# MCU.net
KiCad netlist of a schematic drawn in Altium Designer
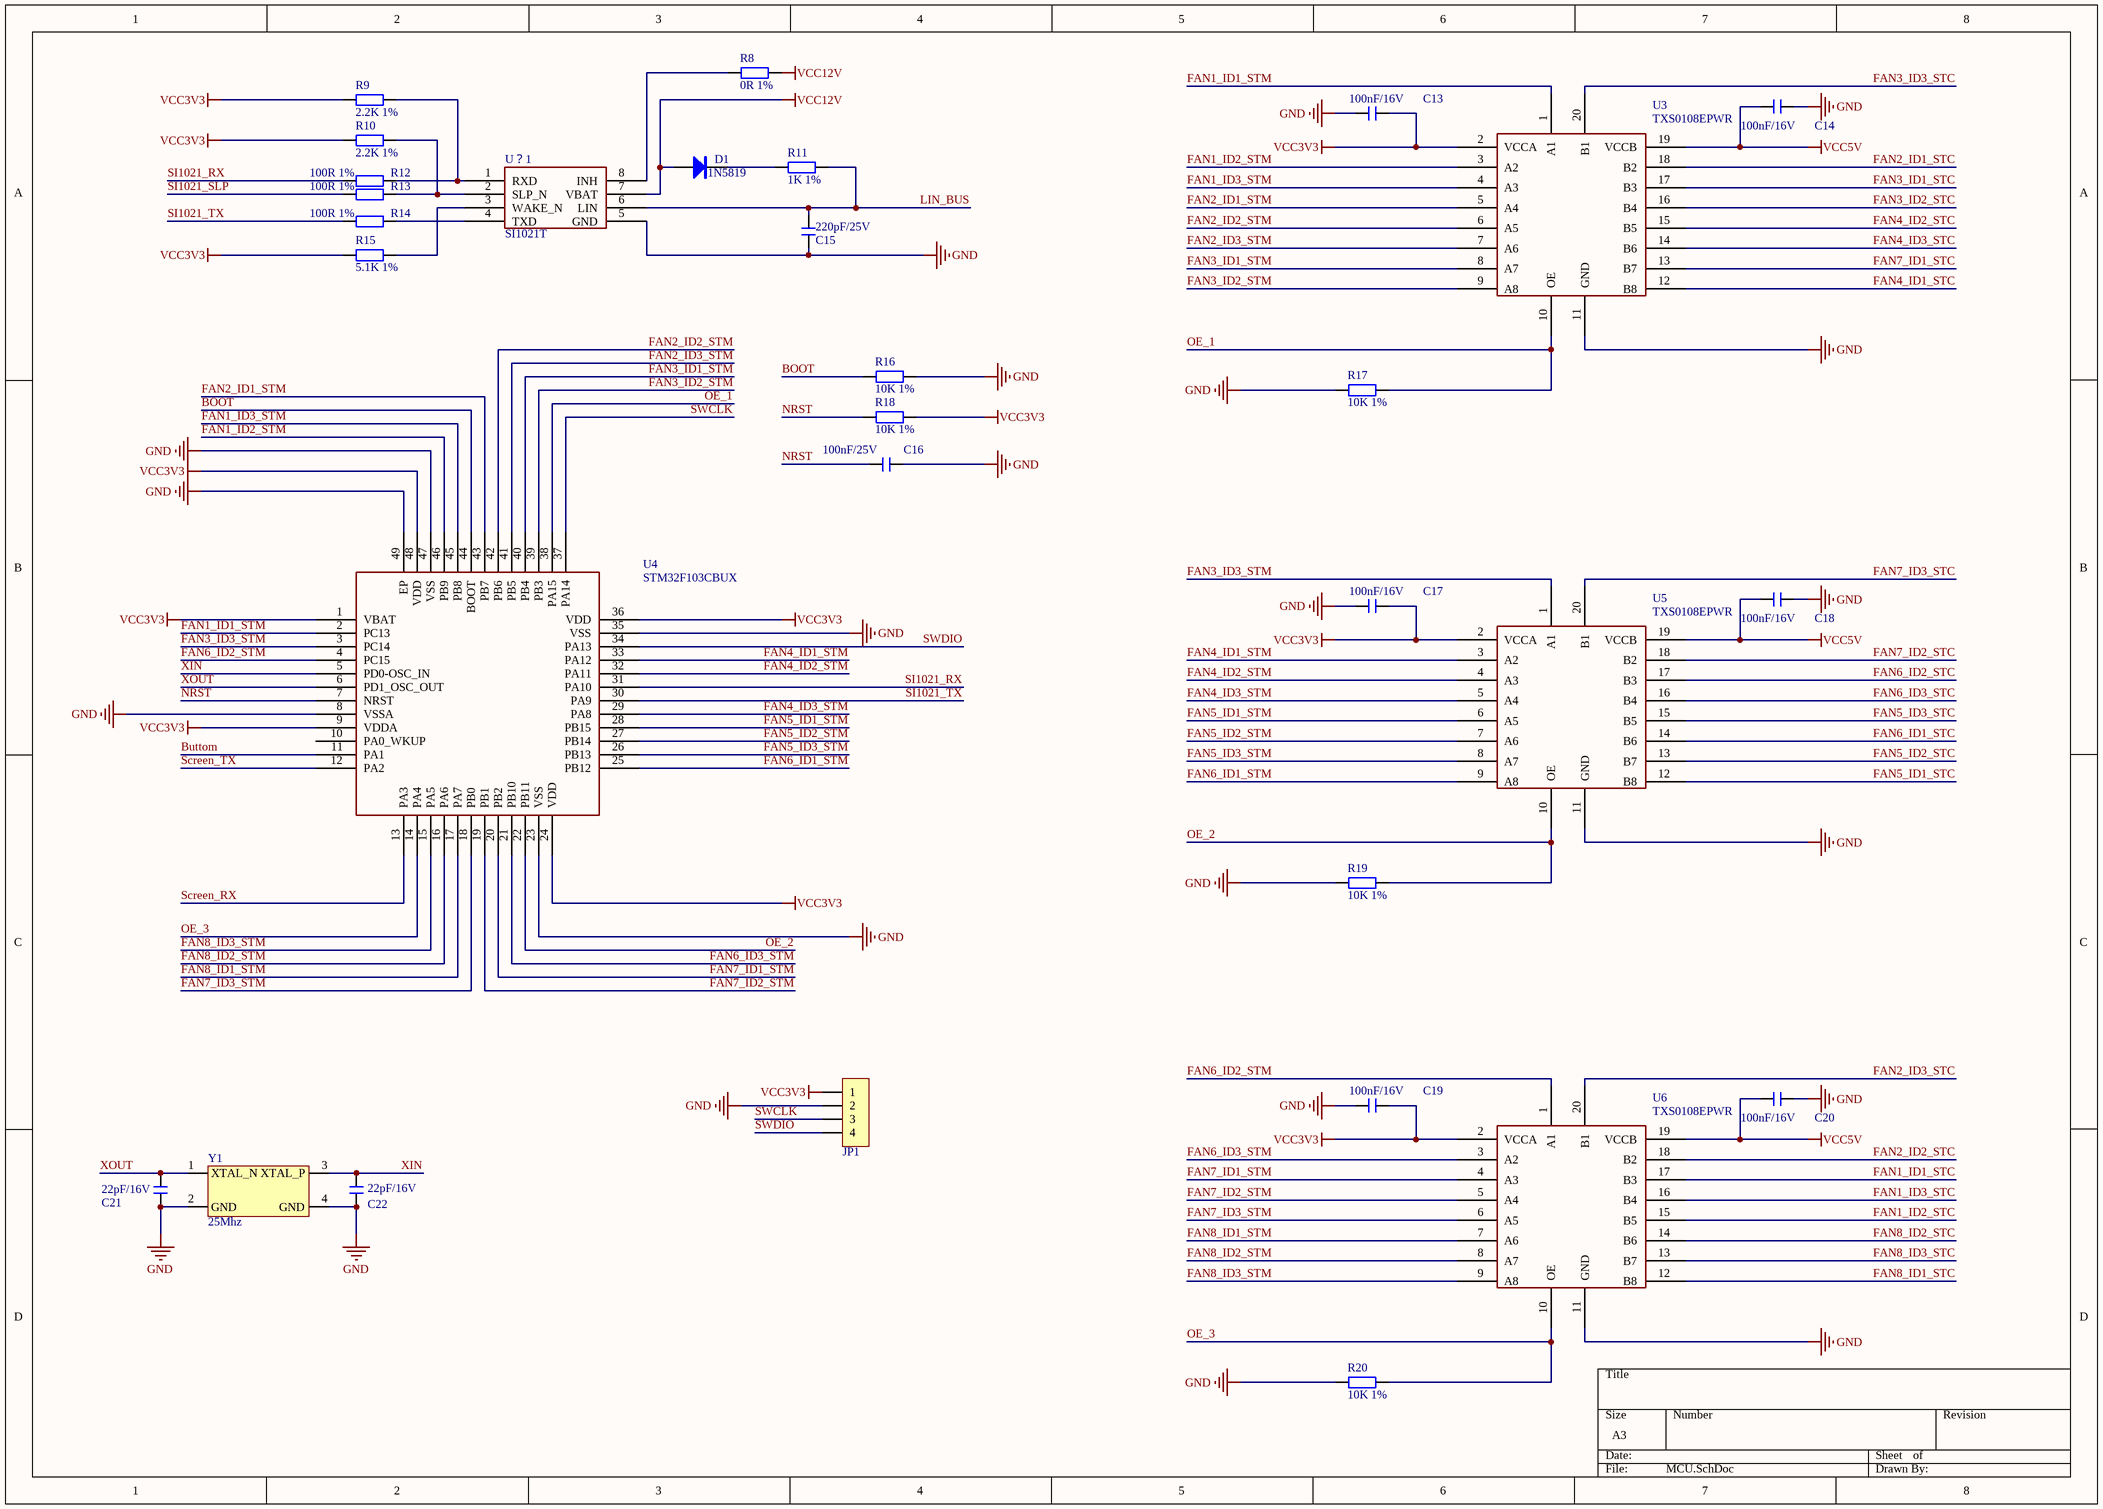
[diagram p0: MCU.SchDoc]

(export (version "E")
  (design (tool "Eeschema 10.0.6"))
  (components
    (comp (ref "C13")
      (value "100nF/16V")
      (footprint "c0603_l")
      (description "无极性贴片电容")
      (fields (field (name "版权归属") "源创客"))
      (libsource (lib "Capacitor") (part "C"))
    )
    (comp (ref "C14")
      (value "100nF/16V")
      (footprint "c0603_l")
      (description "无极性贴片电容")
      (fields (field (name "版权归属") "源创客"))
      (libsource (lib "Capacitor") (part "C"))
    )
    (comp (ref "C15")
      (value "220pF/25V")
      (footprint "c0603_l")
      (description "无极性贴片电容")
      (fields (field (name "版权归属") "源创客"))
      (libsource (lib "Capacitor") (part "C"))
    )
    (comp (ref "C16")
      (value "100nF/25V")
      (footprint "c0603_l")
      (description "无极性贴片电容")
      (fields (field (name "版权归属") "源创客"))
      (libsource (lib "Capacitor") (part "C"))
    )
    (comp (ref "C17")
      (value "100nF/16V")
      (footprint "c0603_l")
      (description "无极性贴片电容")
      (fields (field (name "版权归属") "源创客"))
      (libsource (lib "Capacitor") (part "C"))
    )
    (comp (ref "C18")
      (value "100nF/16V")
      (footprint "c0603_l")
      (description "无极性贴片电容")
      (fields (field (name "版权归属") "源创客"))
      (libsource (lib "Capacitor") (part "C"))
    )
    (comp (ref "C19")
      (value "100nF/16V")
      (footprint "c0603_l")
      (description "无极性贴片电容")
      (fields (field (name "版权归属") "源创客"))
      (libsource (lib "Capacitor") (part "C"))
    )
    (comp (ref "C20")
      (value "100nF/16V")
      (footprint "c0603_l")
      (description "无极性贴片电容")
      (fields (field (name "版权归属") "源创客"))
      (libsource (lib "Capacitor") (part "C"))
    )
    (comp (ref "C21")
      (value "22pF/16V")
      (footprint "c0603_l")
      (description "无极性贴片电容")
      (fields (field (name "版权归属") "源创客"))
      (libsource (lib "Capacitor") (part "C"))
    )
    (comp (ref "C22")
      (value "22pF/16V")
      (footprint "c0603_l")
      (description "无极性贴片电容")
      (fields (field (name "版权归属") "源创客"))
      (libsource (lib "Capacitor") (part "C"))
    )
    (comp (ref "D1")
      (value "1N5819")
      (footprint "SOD-323")
      (description "肖特基二极管")
      (fields (field (name "版权归属") "源创客"))
      (libsource (lib "Diode") (part "1N5819"))
    )
    (comp (ref "JP1")
      (value "HDR-1X4")
      (footprint "HDR2.54-WI-4P")
      (description "4P接插件")
      (fields (field (name "版权归属") "源创客"))
      (libsource (lib "Connector-PinHeader") (part "Header 4"))
    )
    (comp (ref "R8")
      (value "0R 1%")
      (footprint "r0603_l")
      (description "贴片电阻")
      (fields (field (name "版权归属") "源创客"))
      (libsource (lib "Resistor") (part "R"))
    )
    (comp (ref "R9")
      (value "2.2K 1%")
      (footprint "r0603_l")
      (description "贴片电阻")
      (fields (field (name "版权归属") "源创客"))
      (libsource (lib "Resistor") (part "R"))
    )
    (comp (ref "R10")
      (value "2.2K 1%")
      (footprint "r0603_l")
      (description "贴片电阻")
      (fields (field (name "版权归属") "源创客"))
      (libsource (lib "Resistor") (part "R"))
    )
    (comp (ref "R11")
      (value "1K 1%")
      (footprint "r0603_l")
      (description "贴片电阻")
      (fields (field (name "版权归属") "源创客"))
      (libsource (lib "Resistor") (part "R"))
    )
    (comp (ref "R12")
      (value "100R 1%")
      (footprint "r0603_l")
      (description "贴片电阻")
      (fields (field (name "版权归属") "源创客"))
      (libsource (lib "Resistor") (part "R"))
    )
    (comp (ref "R13")
      (value "100R 1%")
      (footprint "r0603_l")
      (description "贴片电阻")
      (fields (field (name "版权归属") "源创客"))
      (libsource (lib "Resistor") (part "R"))
    )
    (comp (ref "R14")
      (value "100R 1%")
      (footprint "r0603_l")
      (description "贴片电阻")
      (fields (field (name "版权归属") "源创客"))
      (libsource (lib "Resistor") (part "R"))
    )
    (comp (ref "R15")
      (value "5.1K 1%")
      (footprint "r0603_l")
      (description "贴片电阻")
      (fields (field (name "版权归属") "源创客"))
      (libsource (lib "Resistor") (part "R"))
    )
    (comp (ref "R16")
      (value "10K 1%")
      (footprint "r0603_l")
      (description "贴片电阻")
      (fields (field (name "版权归属") "源创客"))
      (libsource (lib "Resistor") (part "R"))
    )
    (comp (ref "R17")
      (value "10K 1%")
      (footprint "r0603_l")
      (description "贴片电阻")
      (fields (field (name "版权归属") "源创客"))
      (libsource (lib "Resistor") (part "R"))
    )
    (comp (ref "R18")
      (value "10K 1%")
      (footprint "r0603_l")
      (description "贴片电阻")
      (fields (field (name "版权归属") "源创客"))
      (libsource (lib "Resistor") (part "R"))
    )
    (comp (ref "R19")
      (value "10K 1%")
      (footprint "r0603_l")
      (description "贴片电阻")
      (fields (field (name "版权归属") "源创客"))
      (libsource (lib "Resistor") (part "R"))
    )
    (comp (ref "R20")
      (value "10K 1%")
      (footprint "r0603_l")
      (description "贴片电阻")
      (fields (field (name "版权归属") "源创客"))
      (libsource (lib "Resistor") (part "R"))
    )
    (comp (ref "U3")
      (value "TXS0108EPWR")
      (footprint "TXS0108ERGYR")
      (description "适用于开漏和推挽应用的八位双向电压电平转换器")
      (libsource (lib "移位寄存器") (part "TXS0108EPWR"))
    )
    (comp (ref "U4")
      (value "STM32F103CBUX")
      (footprint "QFN48 7X7_M")
      (libsource (lib "MCU") (part "STM32F103CBUX"))
    )
    (comp (ref "U5")
      (value "TXS0108EPWR")
      (footprint "TXS0108ERGYR")
      (description "适用于开漏和推挽应用的八位双向电压电平转换器")
      (libsource (lib "移位寄存器") (part "TXS0108EPWR"))
    )
    (comp (ref "U6")
      (value "TXS0108EPWR")
      (footprint "TXS0108ERGYR")
      (description "适用于开漏和推挽应用的八位双向电压电平转换器")
      (libsource (lib "移位寄存器") (part "TXS0108EPWR"))
    )
    (comp (ref "U？1")
      (value "SI1021T")
      (footprint "SOP8")
      (description "SI1021T LIN收发器")
      (libsource (lib "transceiver") (part "SI1021T"))
    )
    (comp (ref "Y1") (value "25Mhz") (footprint "OSC 3225-4P") (libsource (lib "Crystal") (part "Crystal")))
  )
  (nets
    (net (code "1") (name "/BOOT") (class "Default")
      (node (ref "R16") (pin "1") (pinfunction "1_1") (pintype "passive"))
      (node (ref "U4") (pin "44") (pinfunction "BOOT_44") (pintype "passive"))
    )
    (net (code "2") (name "/Buttom") (class "Default")
      (node (ref "U4") (pin "11") (pinfunction "PA1_11") (pintype "passive"))
    )
    (net (code "3") (name "/FAN1_ID1_STC") (class "Default")
      (node (ref "U6") (pin "17") (pinfunction "B3_17") (pintype "passive"))
    )
    (net (code "4") (name "/FAN1_ID1_STM") (class "Default")
      (node (ref "U3") (pin "1") (pinfunction "A1_1") (pintype "passive"))
      (node (ref "U4") (pin "2") (pinfunction "PC13_2") (pintype "passive"))
    )
    (net (code "5") (name "/FAN1_ID2_STC") (class "Default")
      (node (ref "U6") (pin "15") (pinfunction "B5_15") (pintype "passive"))
    )
    (net (code "6") (name "/FAN1_ID2_STM") (class "Default")
      (node (ref "U3") (pin "3") (pinfunction "A2_3") (pintype "passive"))
      (node (ref "U4") (pin "46") (pinfunction "PB9_46") (pintype "passive"))
    )
    (net (code "7") (name "/FAN1_ID3_STC") (class "Default")
      (node (ref "U6") (pin "16") (pinfunction "B4_16") (pintype "passive"))
    )
    (net (code "8") (name "/FAN1_ID3_STM") (class "Default")
      (node (ref "U3") (pin "4") (pinfunction "A3_4") (pintype "passive"))
      (node (ref "U4") (pin "45") (pinfunction "PB8_45") (pintype "passive"))
    )
    (net (code "9") (name "/FAN2_ID1_STC") (class "Default")
      (node (ref "U3") (pin "18") (pinfunction "B2_18") (pintype "passive"))
    )
    (net (code "10") (name "/FAN2_ID1_STM") (class "Default")
      (node (ref "U3") (pin "5") (pinfunction "A4_5") (pintype "passive"))
      (node (ref "U4") (pin "43") (pinfunction "PB7_43") (pintype "passive"))
    )
    (net (code "11") (name "/FAN2_ID2_STC") (class "Default")
      (node (ref "U6") (pin "18") (pinfunction "B2_18") (pintype "passive"))
    )
    (net (code "12") (name "/FAN2_ID2_STM") (class "Default")
      (node (ref "U3") (pin "6") (pinfunction "A5_6") (pintype "passive"))
      (node (ref "U4") (pin "42") (pinfunction "PB6_42") (pintype "passive"))
    )
    (net (code "13") (name "/FAN2_ID3_STC") (class "Default")
      (node (ref "U6") (pin "20") (pinfunction "B1_20") (pintype "passive"))
    )
    (net (code "14") (name "/FAN2_ID3_STM") (class "Default")
      (node (ref "U3") (pin "7") (pinfunction "A6_7") (pintype "passive"))
      (node (ref "U4") (pin "41") (pinfunction "PB5_41") (pintype "passive"))
    )
    (net (code "15") (name "/FAN3_ID1_STC") (class "Default")
      (node (ref "U3") (pin "17") (pinfunction "B3_17") (pintype "passive"))
    )
    (net (code "16") (name "/FAN3_ID1_STM") (class "Default")
      (node (ref "U3") (pin "8") (pinfunction "A7_8") (pintype "passive"))
      (node (ref "U4") (pin "40") (pinfunction "PB4_40") (pintype "passive"))
    )
    (net (code "17") (name "/FAN3_ID2_STC") (class "Default")
      (node (ref "U3") (pin "16") (pinfunction "B4_16") (pintype "passive"))
    )
    (net (code "18") (name "/FAN3_ID2_STM") (class "Default")
      (node (ref "U3") (pin "9") (pinfunction "A8_9") (pintype "passive"))
      (node (ref "U4") (pin "39") (pinfunction "PB3_39") (pintype "passive"))
    )
    (net (code "19") (name "/FAN3_ID3_STC") (class "Default")
      (node (ref "U3") (pin "20") (pinfunction "B1_20") (pintype "passive"))
    )
    (net (code "20") (name "/FAN3_ID3_STM") (class "Default")
      (node (ref "U4") (pin "3") (pinfunction "PC14_3") (pintype "passive"))
      (node (ref "U5") (pin "1") (pinfunction "A1_1") (pintype "passive"))
    )
    (net (code "21") (name "/FAN4_ID1_STC") (class "Default")
      (node (ref "U3") (pin "12") (pinfunction "B8_12") (pintype "passive"))
    )
    (net (code "22") (name "/FAN4_ID1_STM") (class "Default")
      (node (ref "U4") (pin "33") (pinfunction "PA12_33") (pintype "passive"))
      (node (ref "U5") (pin "3") (pinfunction "A2_3") (pintype "passive"))
    )
    (net (code "23") (name "/FAN4_ID2_STC") (class "Default")
      (node (ref "U3") (pin "15") (pinfunction "B5_15") (pintype "passive"))
    )
    (net (code "24") (name "/FAN4_ID2_STM") (class "Default")
      (node (ref "U4") (pin "32") (pinfunction "PA11_32") (pintype "passive"))
      (node (ref "U5") (pin "4") (pinfunction "A3_4") (pintype "passive"))
    )
    (net (code "25") (name "/FAN4_ID3_STC") (class "Default")
      (node (ref "U3") (pin "14") (pinfunction "B6_14") (pintype "passive"))
    )
    (net (code "26") (name "/FAN4_ID3_STM") (class "Default")
      (node (ref "U4") (pin "29") (pinfunction "PA8_29") (pintype "passive"))
      (node (ref "U5") (pin "5") (pinfunction "A4_5") (pintype "passive"))
    )
    (net (code "27") (name "/FAN5_ID1_STC") (class "Default")
      (node (ref "U5") (pin "12") (pinfunction "B8_12") (pintype "passive"))
    )
    (net (code "28") (name "/FAN5_ID1_STM") (class "Default")
      (node (ref "U4") (pin "28") (pinfunction "PB15_28") (pintype "passive"))
      (node (ref "U5") (pin "6") (pinfunction "A5_6") (pintype "passive"))
    )
    (net (code "29") (name "/FAN5_ID2_STC") (class "Default")
      (node (ref "U5") (pin "13") (pinfunction "B7_13") (pintype "passive"))
    )
    (net (code "30") (name "/FAN5_ID2_STM") (class "Default")
      (node (ref "U4") (pin "27") (pinfunction "PB14_27") (pintype "passive"))
      (node (ref "U5") (pin "7") (pinfunction "A6_7") (pintype "passive"))
    )
    (net (code "31") (name "/FAN5_ID3_STC") (class "Default")
      (node (ref "U5") (pin "15") (pinfunction "B5_15") (pintype "passive"))
    )
    (net (code "32") (name "/FAN5_ID3_STM") (class "Default")
      (node (ref "U4") (pin "26") (pinfunction "PB13_26") (pintype "passive"))
      (node (ref "U5") (pin "8") (pinfunction "A7_8") (pintype "passive"))
    )
    (net (code "33") (name "/FAN6_ID1_STC") (class "Default")
      (node (ref "U5") (pin "14") (pinfunction "B6_14") (pintype "passive"))
    )
    (net (code "34") (name "/FAN6_ID1_STM") (class "Default")
      (node (ref "U4") (pin "25") (pinfunction "PB12_25") (pintype "passive"))
      (node (ref "U5") (pin "9") (pinfunction "A8_9") (pintype "passive"))
    )
    (net (code "35") (name "/FAN6_ID2_STC") (class "Default")
      (node (ref "U5") (pin "17") (pinfunction "B3_17") (pintype "passive"))
    )
    (net (code "36") (name "/FAN6_ID2_STM") (class "Default")
      (node (ref "U4") (pin "4") (pinfunction "PC15_4") (pintype "passive"))
      (node (ref "U6") (pin "1") (pinfunction "A1_1") (pintype "passive"))
    )
    (net (code "37") (name "/FAN6_ID3_STC") (class "Default")
      (node (ref "U5") (pin "16") (pinfunction "B4_16") (pintype "passive"))
    )
    (net (code "38") (name "/FAN6_ID3_STM") (class "Default")
      (node (ref "U4") (pin "21") (pinfunction "PB10_21") (pintype "passive"))
      (node (ref "U6") (pin "3") (pinfunction "A2_3") (pintype "passive"))
    )
    (net (code "39") (name "/FAN7_ID1_STC") (class "Default")
      (node (ref "U3") (pin "13") (pinfunction "B7_13") (pintype "passive"))
    )
    (net (code "40") (name "/FAN7_ID1_STM") (class "Default")
      (node (ref "U4") (pin "20") (pinfunction "PB2_20") (pintype "passive"))
      (node (ref "U6") (pin "4") (pinfunction "A3_4") (pintype "passive"))
    )
    (net (code "41") (name "/FAN7_ID2_STC") (class "Default")
      (node (ref "U5") (pin "18") (pinfunction "B2_18") (pintype "passive"))
    )
    (net (code "42") (name "/FAN7_ID2_STM") (class "Default")
      (node (ref "U4") (pin "19") (pinfunction "PB1_19") (pintype "passive"))
      (node (ref "U6") (pin "5") (pinfunction "A4_5") (pintype "passive"))
    )
    (net (code "43") (name "/FAN7_ID3_STC") (class "Default")
      (node (ref "U5") (pin "20") (pinfunction "B1_20") (pintype "passive"))
    )
    (net (code "44") (name "/FAN7_ID3_STM") (class "Default")
      (node (ref "U4") (pin "18") (pinfunction "PB0_18") (pintype "passive"))
      (node (ref "U6") (pin "6") (pinfunction "A5_6") (pintype "passive"))
    )
    (net (code "45") (name "/FAN8_ID1_STC") (class "Default")
      (node (ref "U6") (pin "12") (pinfunction "B8_12") (pintype "passive"))
    )
    (net (code "46") (name "/FAN8_ID1_STM") (class "Default")
      (node (ref "U4") (pin "17") (pinfunction "PA7_17") (pintype "passive"))
      (node (ref "U6") (pin "7") (pinfunction "A6_7") (pintype "passive"))
    )
    (net (code "47") (name "/FAN8_ID2_STC") (class "Default")
      (node (ref "U6") (pin "14") (pinfunction "B6_14") (pintype "passive"))
    )
    (net (code "48") (name "/FAN8_ID2_STM") (class "Default")
      (node (ref "U4") (pin "16") (pinfunction "PA6_16") (pintype "passive"))
      (node (ref "U6") (pin "8") (pinfunction "A7_8") (pintype "passive"))
    )
    (net (code "49") (name "/FAN8_ID3_STC") (class "Default")
      (node (ref "U6") (pin "13") (pinfunction "B7_13") (pintype "passive"))
    )
    (net (code "50") (name "/FAN8_ID3_STM") (class "Default")
      (node (ref "U4") (pin "15") (pinfunction "PA5_15") (pintype "passive"))
      (node (ref "U6") (pin "9") (pinfunction "A8_9") (pintype "passive"))
    )
    (net (code "51") (name "/LIN_BUS") (class "Default")
      (node (ref "C15") (pin "2") (pinfunction "2_2") (pintype "passive"))
      (node (ref "R11") (pin "1") (pinfunction "1_1") (pintype "passive"))
      (node (ref "U？1") (pin "6") (pinfunction "LIN_6") (pintype "passive"))
    )
    (net (code "52") (name "/NRST") (class "Default")
      (node (ref "C16") (pin "2") (pinfunction "2_2") (pintype "passive"))
      (node (ref "R18") (pin "1") (pinfunction "1_1") (pintype "passive"))
      (node (ref "U4") (pin "7") (pinfunction "NRST_7") (pintype "passive"))
    )
    (net (code "53") (name "/OE_1") (class "Default")
      (node (ref "R17") (pin "2") (pinfunction "2_2") (pintype "passive"))
      (node (ref "U3") (pin "10") (pinfunction "OE_10") (pintype "passive"))
      (node (ref "U4") (pin "38") (pinfunction "PA15_38") (pintype "passive"))
    )
    (net (code "54") (name "/OE_2") (class "Default")
      (node (ref "R19") (pin "2") (pinfunction "2_2") (pintype "passive"))
      (node (ref "U4") (pin "22") (pinfunction "PB11_22") (pintype "passive"))
      (node (ref "U5") (pin "10") (pinfunction "OE_10") (pintype "passive"))
    )
    (net (code "55") (name "/OE_3") (class "Default")
      (node (ref "R20") (pin "2") (pinfunction "2_2") (pintype "passive"))
      (node (ref "U4") (pin "14") (pinfunction "PA4_14") (pintype "passive"))
      (node (ref "U6") (pin "10") (pinfunction "OE_10") (pintype "passive"))
    )
    (net (code "56") (name "/SI1021_RX") (class "Default")
      (node (ref "R12") (pin "1") (pinfunction "1_1") (pintype "passive"))
      (node (ref "U4") (pin "31") (pinfunction "PA10_31") (pintype "passive"))
    )
    (net (code "57") (name "/SI1021_SLP") (class "Default")
      (node (ref "R13") (pin "1") (pinfunction "1_1") (pintype "passive"))
    )
    (net (code "58") (name "/SI1021_TX") (class "Default")
      (node (ref "R14") (pin "1") (pinfunction "1_1") (pintype "passive"))
      (node (ref "U4") (pin "30") (pinfunction "PA9_30") (pintype "passive"))
    )
    (net (code "59") (name "/SWCLK") (class "Default")
      (node (ref "JP1") (pin "3") (pinfunction "3_3") (pintype "passive"))
      (node (ref "U4") (pin "37") (pinfunction "PA14_37") (pintype "passive"))
    )
    (net (code "60") (name "/SWDIO") (class "Default")
      (node (ref "JP1") (pin "4") (pinfunction "4_4") (pintype "passive"))
      (node (ref "U4") (pin "34") (pinfunction "PA13_34") (pintype "passive"))
    )
    (net (code "61") (name "/Screen_RX") (class "Default")
      (node (ref "U4") (pin "13") (pinfunction "PA3_13") (pintype "passive"))
    )
    (net (code "62") (name "/Screen_TX") (class "Default")
      (node (ref "U4") (pin "12") (pinfunction "PA2_12") (pintype "passive"))
    )
    (net (code "63") (name "/XIN") (class "Default")
      (node (ref "C22") (pin "1") (pinfunction "1_1") (pintype "passive"))
      (node (ref "U4") (pin "5") (pinfunction "PD0-OSC_IN_5") (pintype "passive"))
      (node (ref "Y1") (pin "3") (pinfunction "XTAL_P_3") (pintype "passive"))
    )
    (net (code "64") (name "/XOUT") (class "Default")
      (node (ref "C21") (pin "1") (pinfunction "1_1") (pintype "passive"))
      (node (ref "U4") (pin "6") (pinfunction "PD1_OSC_OUT_6") (pintype "passive"))
      (node (ref "Y1") (pin "1") (pinfunction "XTAL_N_1") (pintype "passive"))
    )
    (net (code "65") (name "GND") (class "Default")
      (node (ref "C13") (pin "2") (pinfunction "2_2") (pintype "passive"))
      (node (ref "C14") (pin "1") (pinfunction "1_1") (pintype "passive"))
      (node (ref "C15") (pin "1") (pinfunction "1_1") (pintype "passive"))
      (node (ref "C16") (pin "1") (pinfunction "1_1") (pintype "passive"))
      (node (ref "C17") (pin "2") (pinfunction "2_2") (pintype "passive"))
      (node (ref "C18") (pin "1") (pinfunction "1_1") (pintype "passive"))
      (node (ref "C19") (pin "2") (pinfunction "2_2") (pintype "passive"))
      (node (ref "C20") (pin "1") (pinfunction "1_1") (pintype "passive"))
      (node (ref "C21") (pin "2") (pinfunction "2_2") (pintype "passive"))
      (node (ref "C22") (pin "2") (pinfunction "2_2") (pintype "passive"))
      (node (ref "JP1") (pin "2") (pinfunction "2_2") (pintype "passive"))
      (node (ref "R16") (pin "2") (pinfunction "2_2") (pintype "passive"))
      (node (ref "R17") (pin "1") (pinfunction "1_1") (pintype "passive"))
      (node (ref "R19") (pin "1") (pinfunction "1_1") (pintype "passive"))
      (node (ref "R20") (pin "1") (pinfunction "1_1") (pintype "passive"))
      (node (ref "U3") (pin "11") (pinfunction "GND_11") (pintype "passive"))
      (node (ref "U4") (pin "23") (pinfunction "VSS_23") (pintype "passive"))
      (node (ref "U4") (pin "35") (pinfunction "VSS_35") (pintype "passive"))
      (node (ref "U4") (pin "47") (pinfunction "VSS_47") (pintype "passive"))
      (node (ref "U4") (pin "49") (pinfunction "EP_49") (pintype "passive"))
      (node (ref "U4") (pin "8") (pinfunction "VSSA_8") (pintype "passive"))
      (node (ref "U5") (pin "11") (pinfunction "GND_11") (pintype "passive"))
      (node (ref "U6") (pin "11") (pinfunction "GND_11") (pintype "passive"))
      (node (ref "U？1") (pin "5") (pinfunction "GND_5") (pintype "passive"))
      (node (ref "Y1") (pin "2") (pinfunction "GND_2") (pintype "passive"))
      (node (ref "Y1") (pin "4") (pinfunction "GND_4") (pintype "passive"))
    )
    (net (code "66") (name "Net-(D1-K)") (class "Default")
      (node (ref "D1") (pin "2") (pinfunction "K_2") (pintype "passive"))
      (node (ref "R11") (pin "2") (pinfunction "2_2") (pintype "passive"))
    )
    (net (code "67") (name "Net-(U？1-INH)") (class "Default")
      (node (ref "R8") (pin "2") (pinfunction "2_2") (pintype "passive"))
      (node (ref "U？1") (pin "8") (pinfunction "INH_8") (pintype "passive"))
    )
    (net (code "68") (name "Net-(U？1-RXD)") (class "Default")
      (node (ref "R12") (pin "2") (pinfunction "2_2") (pintype "passive"))
      (node (ref "R9") (pin "1") (pinfunction "1_1") (pintype "passive"))
      (node (ref "U？1") (pin "1") (pinfunction "RXD_1") (pintype "passive"))
    )
    (net (code "69") (name "Net-(U？1-SLP_N)") (class "Default")
      (node (ref "R10") (pin "1") (pinfunction "1_1") (pintype "passive"))
      (node (ref "R13") (pin "2") (pinfunction "2_2") (pintype "passive"))
      (node (ref "U？1") (pin "2") (pinfunction "SLP_N_2") (pintype "passive"))
    )
    (net (code "70") (name "Net-(U？1-TXD)") (class "Default")
      (node (ref "R14") (pin "2") (pinfunction "2_2") (pintype "passive"))
      (node (ref "U？1") (pin "4") (pinfunction "TXD_4") (pintype "passive"))
    )
    (net (code "71") (name "Net-(U？1-WAKE_N)") (class "Default")
      (node (ref "R15") (pin "1") (pinfunction "1_1") (pintype "passive"))
      (node (ref "U？1") (pin "3") (pinfunction "WAKE_N_3") (pintype "passive"))
    )
    (net (code "72") (name "VCC3V3") (class "Default")
      (node (ref "C13") (pin "1") (pinfunction "1_1") (pintype "passive"))
      (node (ref "C17") (pin "1") (pinfunction "1_1") (pintype "passive"))
      (node (ref "C19") (pin "1") (pinfunction "1_1") (pintype "passive"))
      (node (ref "JP1") (pin "1") (pinfunction "1_1") (pintype "passive"))
      (node (ref "R10") (pin "2") (pinfunction "2_2") (pintype "passive"))
      (node (ref "R15") (pin "2") (pinfunction "2_2") (pintype "passive"))
      (node (ref "R18") (pin "2") (pinfunction "2_2") (pintype "passive"))
      (node (ref "R9") (pin "2") (pinfunction "2_2") (pintype "passive"))
      (node (ref "U3") (pin "2") (pinfunction "VCCA_2") (pintype "passive"))
      (node (ref "U4") (pin "1") (pinfunction "VBAT_1") (pintype "passive"))
      (node (ref "U4") (pin "24") (pinfunction "VDD_24") (pintype "passive"))
      (node (ref "U4") (pin "36") (pinfunction "VDD_36") (pintype "passive"))
      (node (ref "U4") (pin "48") (pinfunction "VDD_48") (pintype "passive"))
      (node (ref "U4") (pin "9") (pinfunction "VDDA_9") (pintype "passive"))
      (node (ref "U5") (pin "2") (pinfunction "VCCA_2") (pintype "passive"))
      (node (ref "U6") (pin "2") (pinfunction "VCCA_2") (pintype "passive"))
    )
    (net (code "73") (name "VCC5V") (class "Default")
      (node (ref "C14") (pin "2") (pinfunction "2_2") (pintype "passive"))
      (node (ref "C18") (pin "2") (pinfunction "2_2") (pintype "passive"))
      (node (ref "C20") (pin "2") (pinfunction "2_2") (pintype "passive"))
      (node (ref "U3") (pin "19") (pinfunction "VCCB_19") (pintype "passive"))
      (node (ref "U5") (pin "19") (pinfunction "VCCB_19") (pintype "passive"))
      (node (ref "U6") (pin "19") (pinfunction "VCCB_19") (pintype "passive"))
    )
    (net (code "74") (name "VCC12V") (class "Default")
      (node (ref "D1") (pin "1") (pinfunction "A_1") (pintype "passive"))
      (node (ref "R8") (pin "1") (pinfunction "1_1") (pintype "passive"))
      (node (ref "U？1") (pin "7") (pinfunction "VBAT_7") (pintype "passive"))
    )
    (net (code "75") (name "unconnected-(U4-PA0_WKUP-Pad10)") (class "Default")
      (node (ref "U4") (pin "10") (pinfunction "PA0_WKUP_10") (pintype "passive"))
    )
  )
)
